# CompSchm.net
KiCad netlist of a schematic drawn in Altium Designer
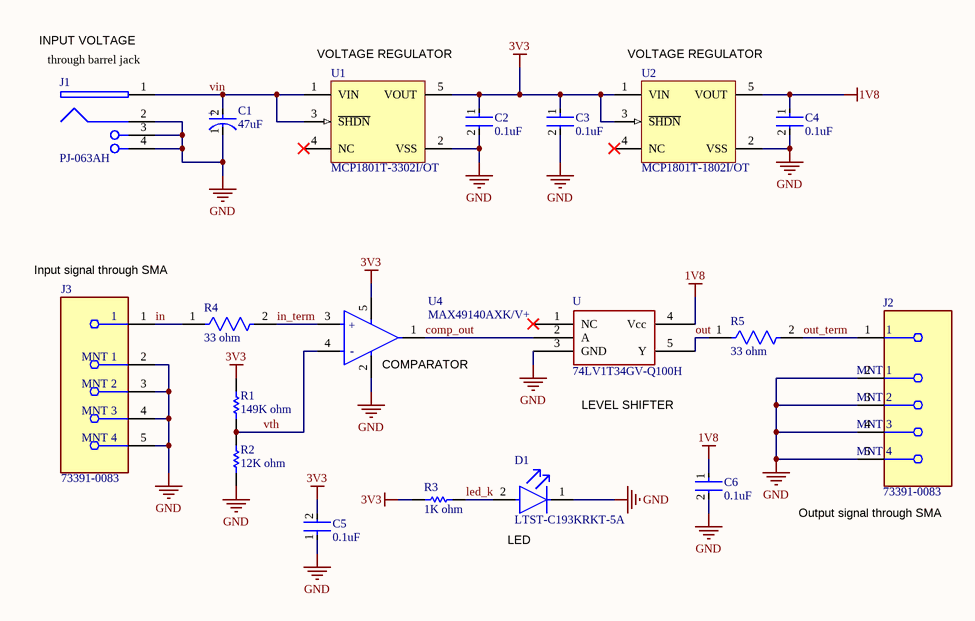
[diagram p0: CompSchm.SchDoc]

(export (version "E")
  (design (tool "Eeschema 10.0.6"))
  (components
    (comp (ref "C1")
      (value "47uF")
      (footprint "FP-T491X476K035AT-MFG")
      (description "CAP TANT 47UF 10% 35V 2917 Part: T491X476K035AT")
      (fields (field (name "TOLERANCE") "10%") (field (name "VOLTAGE") "35V"))
      (libsource (lib "Altium Content Vault") (part "203bc49f2ac43e59fd269a8c329ed05"))
    )
    (comp (ref "C2")
      (value "0.1uF")
      (footprint "FP-CL21-IPC_C")
      (description "CL21 Series 0805 100nF 25V ±10% Tolerance X7R Multilayer Ceramic Chip Capacitor")
      (fields (field (name "VOLTAGE") "25V") (field (name "TOLERANCE") "10%"))
      (libsource (lib "Altium Content Vault") (part "b4654b650e69147ec39a6b967a45e02"))
    )
    (comp (ref "C3")
      (value "0.1uF")
      (footprint "FP-CL21-IPC_C")
      (description "CL21 Series 0805 100nF 25V ±10% Tolerance X7R Multilayer Ceramic Chip Capacitor")
      (fields (field (name "VOLTAGE") "25V") (field (name "TOLERANCE") "10%"))
      (libsource (lib "Altium Content Vault") (part "b4654b650e69147ec39a6b967a45e02"))
    )
    (comp (ref "C4")
      (value "0.1uF")
      (footprint "FP-CL21-IPC_C")
      (description "CL21 Series 0805 100nF 25V ±10% Tolerance X7R Multilayer Ceramic Chip Capacitor")
      (fields (field (name "VOLTAGE") "25V") (field (name "TOLERANCE") "10%"))
      (libsource (lib "Altium Content Vault") (part "b4654b650e69147ec39a6b967a45e02"))
    )
    (comp (ref "C5")
      (value "0.1uF")
      (footprint "FP-CL21-IPC_C")
      (description "CL21 Series 0805 100nF 25V ±10% Tolerance X7R Multilayer Ceramic Chip Capacitor")
      (fields (field (name "VOLTAGE") "25V") (field (name "TOLERANCE") "10%"))
      (libsource (lib "Altium Content Vault") (part "b4654b650e69147ec39a6b967a45e02"))
    )
    (comp (ref "C6")
      (value "0.1uF")
      (footprint "FP-CL21-IPC_C")
      (description "CL21 Series 0805 100nF 25V ±10% Tolerance X7R Multilayer Ceramic Chip Capacitor")
      (fields (field (name "VOLTAGE") "25V") (field (name "TOLERANCE") "10%"))
      (libsource (lib "Altium Content Vault") (part "b4654b650e69147ec39a6b967a45e02"))
    )
    (comp (ref "D1")
      (value "LTST-C193KRKT-5A")
      (footprint "FP-LTST-C193KRKT-5A-MFG")
      (description "LED RED CLEAR CHIP SMD")
      (libsource (lib "Altium Content Vault") (part "8706943c75ba83719d021d2fdc84c58"))
    )
    (comp (ref "J1")
      (value "PJ-063AH")
      (footprint "CUI-PJ-063AH_V")
      (fields (field (name "MANUFACTURER") "CUIInc."))
      (libsource (lib "Altium Content Vault") (part "JACK-2CD2_A"))
    )
    (comp (ref "J2")
      (value "73391-0083")
      (footprint "FP-73391-0083-MFG")
      (description "SMA RA JACK, PCB")
      (libsource (lib "") (part "c65b8a639cdaef1819ea20b5466f8fa_1"))
    )
    (comp (ref "J3")
      (value "73391-0083")
      (footprint "FP-73391-0083-MFG")
      (description "SMA RA JACK, PCB")
      (libsource (lib "Altium Content Vault") (part "c65b8a639cdaef1819ea20b5466f8fa"))
    )
    (comp (ref "R1")
      (value "149K ohm")
      (footprint "RESC2013X50X40NL20T20")
      (fields (field (name "PART NUMBER") "RG2012N-123-W-T1") (field (name "MANUFACTURER") "Susumu"))
      (libsource (lib "Altium Content Vault") (part "RES"))
    )
    (comp (ref "R2")
      (value "12K ohm")
      (footprint "RESC2013X50X40NL20T20")
      (fields (field (name "PART NUMBER") "RG2012N-123-W-T1") (field (name "MANUFACTURER") "Susumu"))
      (libsource (lib "Altium Content Vault") (part "RES"))
    )
    (comp (ref "R3")
      (value "1K ohm")
      (footprint "RESC2013X50X40NL20T20")
      (fields (field (name "PART NUMBER") "RG2012N-123-W-T1") (field (name "MANUFACTURER") "Susumu"))
      (libsource (lib "Altium Content Vault") (part "RES"))
    )
    (comp (ref "R4")
      (value "33 ohm")
      (footprint "FP-CRGCQ0805-IPC_C")
      (description "CRGCQ0805 33Ω 0.125W ±200ppm/°C 1% 150V")
      (fields
        (field (name "MANUFACTURER PART NUMBER") "CRGCQ0805F33R")
        (field (name "MANUFACTURER") "TE Connectivity")
      )
      (libsource (lib "Altium Content Vault") (part "1029c3af85768c4190bb7ad29bc67b5"))
    )
    (comp (ref "R5")
      (value "33 ohm")
      (footprint "FP-CRGCQ0805-IPC_C")
      (description "CRGCQ0805 33Ω 0.125W ±200ppm/°C 1% 150V")
      (fields
        (field (name "MANUFACTURER PART NUMBER") "CRGCQ0805F33R")
        (field (name "MANUFACTURER") "TE Connectivity")
      )
      (libsource (lib "Altium Content Vault") (part "1029c3af85768c4190bb7ad29bc67b5"))
    )
    (comp (ref "U")
      (value "74LV1T34GV-Q100H")
      (footprint "SOT95P275X110-5N:SOT95P275X110-5N")
      (description "Level Shifter")
      (libsource (lib "74LV1T34GV-Q100H") (part "74LV1T34GV-Q100H"))
    )
    (comp (ref "U1")
      (value "MCP1801T-3302I/OT")
      (footprint "SOT-23-OT5_M")
      (description "150 mA, High PSRR, Low Quiescent Current LDO, 5-Pin SOT-23, Industrial Temperature, Tape and Reel")
      (libsource (lib "Altium Content Vault") (part "PM-LINEREG-MCP1801-IL5"))
    )
    (comp (ref "U2")
      (value "MCP1801T-1802I/OT")
      (footprint "SOT-23-OT5_M")
      (description "150 mA, High PSRR, Low Quiescent Current LDO, 5-Pin SOT-23, Industrial Temperature, Tape and Reel")
      (libsource (lib "Altium Content Vault") (part "PM-LINEREG-MCP1801-IL5"))
    )
    (comp (ref "U4")
      (value "MAX49140AXK/V+")
      (footprint "FP-X5-1C-MFG")
      (description "30NS, LOW-POWER, 3V/5V, RAIL-TO-")
      (libsource (lib "Altium Content Vault") (part "3063e83f23e6bb72aa5a98f7fedc5b1"))
    )
  )
  (nets
    (net (code "1") (name "/comp_out") (class "Default")
      (node (ref "U") (pin "2") (pinfunction "A_2") (pintype "passive"))
      (node (ref "U4") (pin "1") (pinfunction "OUT_1") (pintype "passive"))
    )
    (net (code "2") (name "/in") (class "Default")
      (node (ref "J3") (pin "1") (pinfunction "1_1") (pintype "passive"))
      (node (ref "R4") (pin "1") (pinfunction "1_1") (pintype "passive"))
    )
    (net (code "3") (name "/in_term") (class "Default")
      (node (ref "R4") (pin "2") (pinfunction "2_2") (pintype "passive"))
      (node (ref "U4") (pin "3") (pinfunction "IN+_3") (pintype "tri_state"))
    )
    (net (code "4") (name "/led_k") (class "Default")
      (node (ref "D1") (pin "2") (pinfunction "A_2") (pintype "passive"))
      (node (ref "R3") (pin "1") (pinfunction "1_1") (pintype "passive"))
    )
    (net (code "5") (name "/out") (class "Default")
      (node (ref "R5") (pin "1") (pinfunction "1_1") (pintype "passive"))
      (node (ref "U") (pin "5") (pinfunction "Y_5") (pintype "passive"))
    )
    (net (code "6") (name "/out_term") (class "Default")
      (node (ref "J2") (pin "1") (pinfunction "1_1") (pintype "passive"))
      (node (ref "R5") (pin "2") (pinfunction "2_2") (pintype "passive"))
    )
    (net (code "7") (name "/vin") (class "Default")
      (node (ref "C1") (pin "2") (pinfunction "A_2") (pintype "passive"))
      (node (ref "J1") (pin "1") (pinfunction "1_1") (pintype "passive"))
      (node (ref "U1") (pin "1") (pinfunction "VIN_1") (pintype "power_in"))
      (node (ref "U1") (pin "3") (pinfunction "~{SHDN}_3") (pintype "input"))
    )
    (net (code "8") (name "/vth") (class "Default")
      (node (ref "R1") (pin "1") (pinfunction "1_1") (pintype "passive"))
      (node (ref "R2") (pin "2") (pinfunction "2_2") (pintype "passive"))
      (node (ref "U4") (pin "4") (pinfunction "IN-_4") (pintype "tri_state"))
    )
    (net (code "9") (name "1V8") (class "Default")
      (node (ref "C4") (pin "1") (pinfunction "1_1") (pintype "passive"))
      (node (ref "C6") (pin "1") (pinfunction "1_1") (pintype "passive"))
      (node (ref "U") (pin "4") (pinfunction "Vcc_4") (pintype "passive"))
      (node (ref "U2") (pin "5") (pinfunction "VOUT_5") (pintype "power_in"))
    )
    (net (code "10") (name "3V3") (class "Default")
      (node (ref "C2") (pin "1") (pinfunction "1_1") (pintype "passive"))
      (node (ref "C3") (pin "1") (pinfunction "1_1") (pintype "passive"))
      (node (ref "C5") (pin "2") (pinfunction "2_2") (pintype "passive"))
      (node (ref "R1") (pin "2") (pinfunction "2_2") (pintype "passive"))
      (node (ref "R3") (pin "2") (pinfunction "2_2") (pintype "passive"))
      (node (ref "U1") (pin "5") (pinfunction "VOUT_5") (pintype "power_in"))
      (node (ref "U2") (pin "1") (pinfunction "VIN_1") (pintype "power_in"))
      (node (ref "U2") (pin "3") (pinfunction "~{SHDN}_3") (pintype "input"))
      (node (ref "U4") (pin "5") (pinfunction "VDD_5") (pintype "power_in"))
    )
    (net (code "11") (name "GND") (class "Default")
      (node (ref "C1") (pin "1") (pinfunction "C_1") (pintype "passive"))
      (node (ref "C2") (pin "2") (pinfunction "2_2") (pintype "passive"))
      (node (ref "C3") (pin "2") (pinfunction "2_2") (pintype "passive"))
      (node (ref "C4") (pin "2") (pinfunction "2_2") (pintype "passive"))
      (node (ref "C5") (pin "1") (pinfunction "1_1") (pintype "passive"))
      (node (ref "C6") (pin "2") (pinfunction "2_2") (pintype "passive"))
      (node (ref "D1") (pin "1") (pinfunction "C_1") (pintype "passive"))
      (node (ref "J1") (pin "2") (pinfunction "2_2") (pintype "passive"))
      (node (ref "J1") (pin "3") (pinfunction "SHLD_3") (pintype "passive"))
      (node (ref "J1") (pin "4") (pinfunction "SHLD_4") (pintype "passive"))
      (node (ref "J2") (pin "2") (pinfunction "MNT_1_2") (pintype "passive"))
      (node (ref "J2") (pin "3") (pinfunction "MNT_2_3") (pintype "passive"))
      (node (ref "J2") (pin "4") (pinfunction "MNT_3_4") (pintype "passive"))
      (node (ref "J2") (pin "5") (pinfunction "MNT_4_5") (pintype "passive"))
      (node (ref "J3") (pin "2") (pinfunction "MNT_1_2") (pintype "passive"))
      (node (ref "J3") (pin "3") (pinfunction "MNT_2_3") (pintype "passive"))
      (node (ref "J3") (pin "4") (pinfunction "MNT_3_4") (pintype "passive"))
      (node (ref "J3") (pin "5") (pinfunction "MNT_4_5") (pintype "passive"))
      (node (ref "R2") (pin "1") (pinfunction "1_1") (pintype "passive"))
      (node (ref "U") (pin "3") (pinfunction "GND_3") (pintype "passive"))
      (node (ref "U1") (pin "2") (pinfunction "VSS_2") (pintype "power_in"))
      (node (ref "U2") (pin "2") (pinfunction "VSS_2") (pintype "power_in"))
      (node (ref "U4") (pin "2") (pinfunction "GND_2") (pintype "power_in"))
    )
    (net (code "12") (name "unconnected-(U-NC-Pad1)") (class "Default")
      (node (ref "U") (pin "1") (pinfunction "NC_1") (pintype "passive+no_connect"))
    )
    (net (code "13") (name "unconnected-(U1-NC-Pad4)") (class "Default")
      (node (ref "U1") (pin "4") (pinfunction "NC_4") (pintype "passive+no_connect"))
    )
    (net (code "14") (name "unconnected-(U2-NC-Pad4)") (class "Default")
      (node (ref "U2") (pin "4") (pinfunction "NC_4") (pintype "passive+no_connect"))
    )
  )
)
